# MIXR_Interface_-_Buttons.net
KiCad netlist of a schematic drawn in Altium Designer
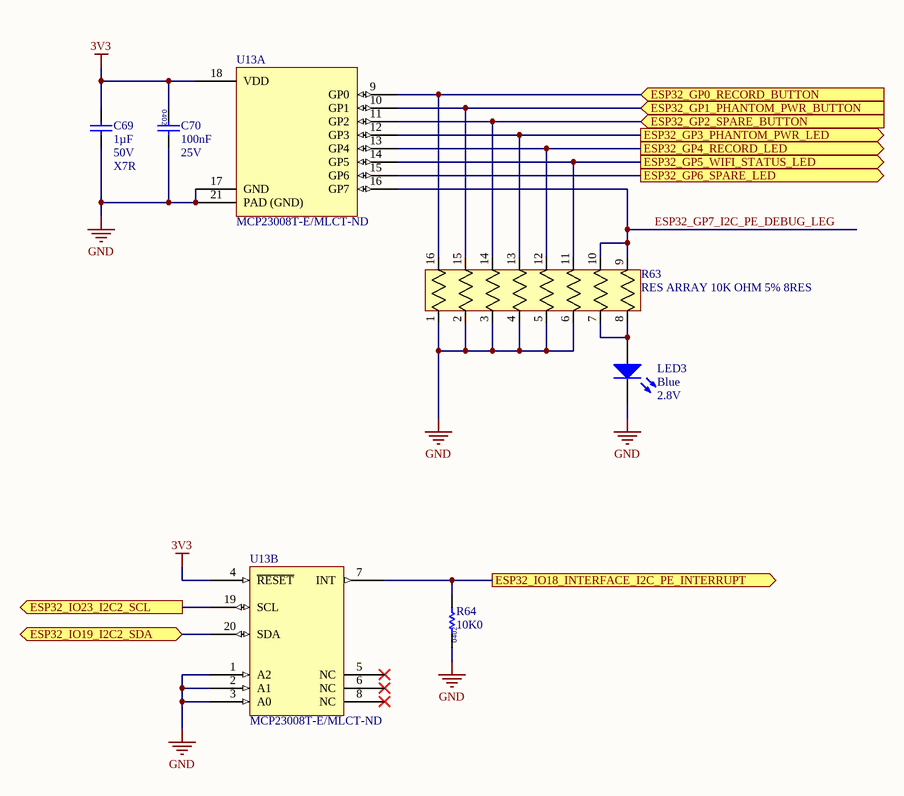
[diagram p0: MIXR Interface - Buttons.SchDoc]

(export (version "E")
  (design (tool "Eeschema 10.0.6"))
  (components
    (comp (ref "C69")
      (value "CAP CER 1UF 50V 10% X7R 0603")
      (footprint "CAP, 0603")
      (description "1µF ±10% 50V Ceramic Capacitor X7R 0603 (1608 Metric)")
      (fields
        (field (name "TOLERANCE") "±10%")
        (field (name "CAPACITANCE") "1µF")
        (field (name "VOLTAGE") "50V")
        (field (name "TEMPERATURE COEFFICIENT") "X7R")
      )
      (libsource (lib "Schematic Diagrams") (part "CAP CER 1UF 50V 10% X7R 0603"))
    )
    (comp (ref "C70")
      (value "CAP CER 0.1UF 16V X7R 0402")
      (footprint "CAP 0402")
      (description "Cap Ceramic 0.1uF 25V X7R 10% SMD 0402 125C Paper T/R")
      (fields
        (field (name "TOLERANCE") "10%")
        (field (name "CAPACITANCE") "100nF")
        (field (name "VOLTAGE") "25V")
        (field (name "MANUFACTURER") "Murata")
      )
      (libsource (lib "Schematic Diagrams") (part "CAP CER 0.1UF 16V X7R 0402"))
    )
    (comp (ref "LED3")
      (value "LED BLUE CLEAR 2.8V 0603")
      (footprint "LED_0603")
      (description "Blue 470nm LED Indication - Discrete 2.8V 0603 (1608 Metric)")
      (fields (field (name "COLOR") "Blue") (field (name "VOLTAGE - FORWARD (VF) (TYP)") "2.8V"))
      (libsource (lib "Schematic Diagrams") (part "LED BLUE CLEAR 2.8V 0603"))
    )
    (comp (ref "R63")
      (value "RES ARRAY 10K OHM 5% 8RES")
      (footprint "RES ARRAY, 8 POS 1506")
      (description "RES ARRAY SMD 10K 5% 62.5mW 1506")
      (fields
        (field (name "MANUFACTURER_PART_NUMBER") "EXB-2HV103JV")
        (field (name "MANUFACTURER") "Panasonic Electronic Components")
        (field (name "COPYRIGHT") "Copyright (C) 2015 Accelerated Designs. All rights reserved")
      )
      (libsource (lib "Schematic Diagrams") (part "RES ARRAY 10K OHM 5% 8RES EXB-2HV103JV"))
    )
    (comp (ref "R64")
      (value "RES 10K OHM 1% 1/16W 0402")
      (footprint "RES 0402")
      (description "Surface Mount Thick Film Resistor, Rc Series, 10 Kohm, 62.5 Mw, - 1%, 50 V, 0402 [1005 Metric]")
      (fields
        (field (name "TOLERANCE") "1%")
        (field (name "RESISTANCE") "10K0")
        (field (name "MANUFACTURER") "Yageo")
      )
      (libsource (lib "Schematic Diagrams") (part "RES 10K OHM 1% 1/16W 0402"))
    )
    (comp (ref "U13")
      (value "MCP23008")
      (footprint "QFN50P400X400X100_HS-21M")
      (description "I/O Expander 8 I²C 1.7MHz 20-QFN-EP (4x4)")
      (fields (field (name "SUPPLIER PART NUMBER 1") "MCP23008T-E/MLCT-ND"))
      (libsource (lib "Schematic Diagrams") (part "IC I/O EXPANDER I2C 8CH 20 QFN"))
    )
  )
  (nets
    (net (code "1") (name "/ESP32_GP0_RECORD_BUTTON") (class "Default")
      (node (ref "R63") (pin "16") (pinfunction "16_16") (pintype "passive"))
      (node (ref "U13") (pin "9") (pinfunction "GP0_9") (pintype "bidirectional"))
    )
    (net (code "2") (name "/ESP32_GP1_PHANTOM_PWR_BUTTON") (class "Default")
      (node (ref "R63") (pin "15") (pinfunction "15_15") (pintype "passive"))
      (node (ref "U13") (pin "10") (pinfunction "GP1_10") (pintype "bidirectional"))
    )
    (net (code "3") (name "/ESP32_GP2_SPARE_BUTTON") (class "Default")
      (node (ref "R63") (pin "14") (pinfunction "14_14") (pintype "passive"))
      (node (ref "U13") (pin "11") (pinfunction "GP2_11") (pintype "bidirectional"))
    )
    (net (code "4") (name "/ESP32_GP3_PHANTOM_PWR_LED") (class "Default")
      (node (ref "R63") (pin "13") (pinfunction "13_13") (pintype "passive"))
      (node (ref "U13") (pin "12") (pinfunction "GP3_12") (pintype "bidirectional"))
    )
    (net (code "5") (name "/ESP32_GP4_RECORD_LED") (class "Default")
      (node (ref "R63") (pin "12") (pinfunction "12_12") (pintype "passive"))
      (node (ref "U13") (pin "13") (pinfunction "GP4_13") (pintype "bidirectional"))
    )
    (net (code "6") (name "/ESP32_GP5_WIFI_STATUS_LED") (class "Default")
      (node (ref "R63") (pin "11") (pinfunction "11_11") (pintype "passive"))
      (node (ref "U13") (pin "14") (pinfunction "GP5_14") (pintype "bidirectional"))
    )
    (net (code "7") (name "/ESP32_GP6_SPARE_LED") (class "Default")
      (node (ref "U13") (pin "15") (pinfunction "GP6_15") (pintype "bidirectional"))
    )
    (net (code "8") (name "/ESP32_GP7_I2C_PE_DEBUG_LEG") (class "Default")
      (node (ref "R63") (pin "10") (pinfunction "10_10") (pintype "passive"))
      (node (ref "R63") (pin "9") (pinfunction "9_9") (pintype "passive"))
      (node (ref "U13") (pin "16") (pinfunction "GP7_16") (pintype "bidirectional"))
    )
    (net (code "9") (name "/ESP32_IO18_INTERFACE_I2C_PE_INTERRUPT") (class "Default")
      (node (ref "R64") (pin "2") (pinfunction "2_2") (pintype "passive"))
      (node (ref "U13") (pin "7") (pinfunction "INT_7") (pintype "output"))
    )
    (net (code "10") (name "/ESP32_IO19_I2C2_SDA") (class "Default")
      (node (ref "U13") (pin "20") (pinfunction "SDA_20") (pintype "bidirectional"))
    )
    (net (code "11") (name "/ESP32_IO23_I2C2_SCL") (class "Default")
      (node (ref "U13") (pin "19") (pinfunction "SCL_19") (pintype "bidirectional"))
    )
    (net (code "12") (name "3V3") (class "Default")
      (node (ref "C69") (pin "1") (pinfunction "1_1") (pintype "passive"))
      (node (ref "C70") (pin "1") (pinfunction "1_1") (pintype "passive"))
      (node (ref "U13") (pin "18") (pinfunction "VDD_18") (pintype "power_in"))
      (node (ref "U13") (pin "4") (pinfunction "~{RESET}_4") (pintype "input"))
    )
    (net (code "13") (name "GND") (class "Default")
      (node (ref "C69") (pin "2") (pinfunction "2_2") (pintype "passive"))
      (node (ref "C70") (pin "2") (pinfunction "2_2") (pintype "passive"))
      (node (ref "LED3") (pin "2") (pinfunction "K_2") (pintype "passive"))
      (node (ref "R63") (pin "1") (pinfunction "1_1") (pintype "passive"))
      (node (ref "R63") (pin "2") (pinfunction "2_2") (pintype "passive"))
      (node (ref "R63") (pin "3") (pinfunction "3_3") (pintype "passive"))
      (node (ref "R63") (pin "4") (pinfunction "4_4") (pintype "passive"))
      (node (ref "R63") (pin "5") (pinfunction "5_5") (pintype "passive"))
      (node (ref "R63") (pin "6") (pinfunction "6_6") (pintype "passive"))
      (node (ref "R64") (pin "1") (pinfunction "1_1") (pintype "passive"))
      (node (ref "U13") (pin "1") (pinfunction "A2_1") (pintype "input"))
      (node (ref "U13") (pin "17") (pinfunction "GND_17") (pintype "power_in"))
      (node (ref "U13") (pin "2") (pinfunction "A1_2") (pintype "input"))
      (node (ref "U13") (pin "21") (pinfunction "PAD_(GND)_21") (pintype "power_in"))
      (node (ref "U13") (pin "3") (pinfunction "A0_3") (pintype "input"))
    )
    (net (code "14") (name "Net-(LED3-A)") (class "Default")
      (node (ref "LED3") (pin "1") (pinfunction "A_1") (pintype "passive"))
      (node (ref "R63") (pin "7") (pinfunction "7_7") (pintype "passive"))
      (node (ref "R63") (pin "8") (pinfunction "8_8") (pintype "passive"))
    )
    (net (code "15") (name "unconnected-(U13B-NC-Pad5)") (class "Default")
      (node (ref "U13") (pin "5") (pinfunction "NC_5") (pintype "passive+no_connect"))
    )
    (net (code "16") (name "unconnected-(U13B-NC-Pad6)") (class "Default")
      (node (ref "U13") (pin "6") (pinfunction "NC_6") (pintype "passive+no_connect"))
    )
    (net (code "17") (name "unconnected-(U13B-NC-Pad8)") (class "Default")
      (node (ref "U13") (pin "8") (pinfunction "NC_8") (pintype "passive+no_connect"))
    )
  )
)
